# US100.net
KiCad netlist of a schematic drawn in Altium Designer
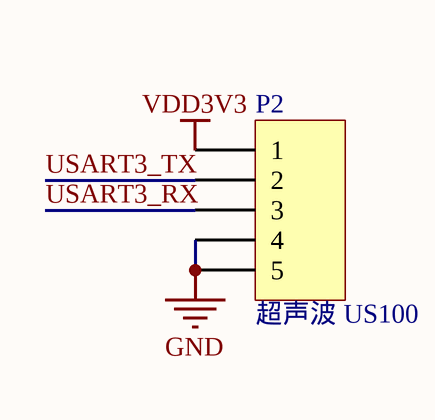
[diagram p0: US100.SchDoc]

(export (version "E")
  (design (tool "Eeschema 10.0.6"))
  (components
    (comp (ref "P2")
      (value "超声波 US100")
      (footprint "HDR1X5")
      (description "Header, 5-Pin")
      (fields (field (name "PUBLISHER") "Altium Limited"))
      (libsource (lib "Miscellaneous Connectors") (part "Header 5"))
    )
  )
  (nets
    (net (code "1") (name "/USART3_RX") (class "Default")
      (node (ref "P2") (pin "3") (pinfunction "3_3") (pintype "passive"))
    )
    (net (code "2") (name "/USART3_TX") (class "Default")
      (node (ref "P2") (pin "2") (pinfunction "2_2") (pintype "passive"))
    )
    (net (code "3") (name "GND") (class "Default")
      (node (ref "P2") (pin "4") (pinfunction "4_4") (pintype "passive"))
      (node (ref "P2") (pin "5") (pinfunction "5_5") (pintype "passive"))
    )
    (net (code "4") (name "VDD3V3") (class "Default")
      (node (ref "P2") (pin "1") (pinfunction "1_1") (pintype "passive"))
    )
  )
)
